# LuxLogger_V2_mcu_pwr.net
KiCad netlist of a schematic drawn in Altium Designer
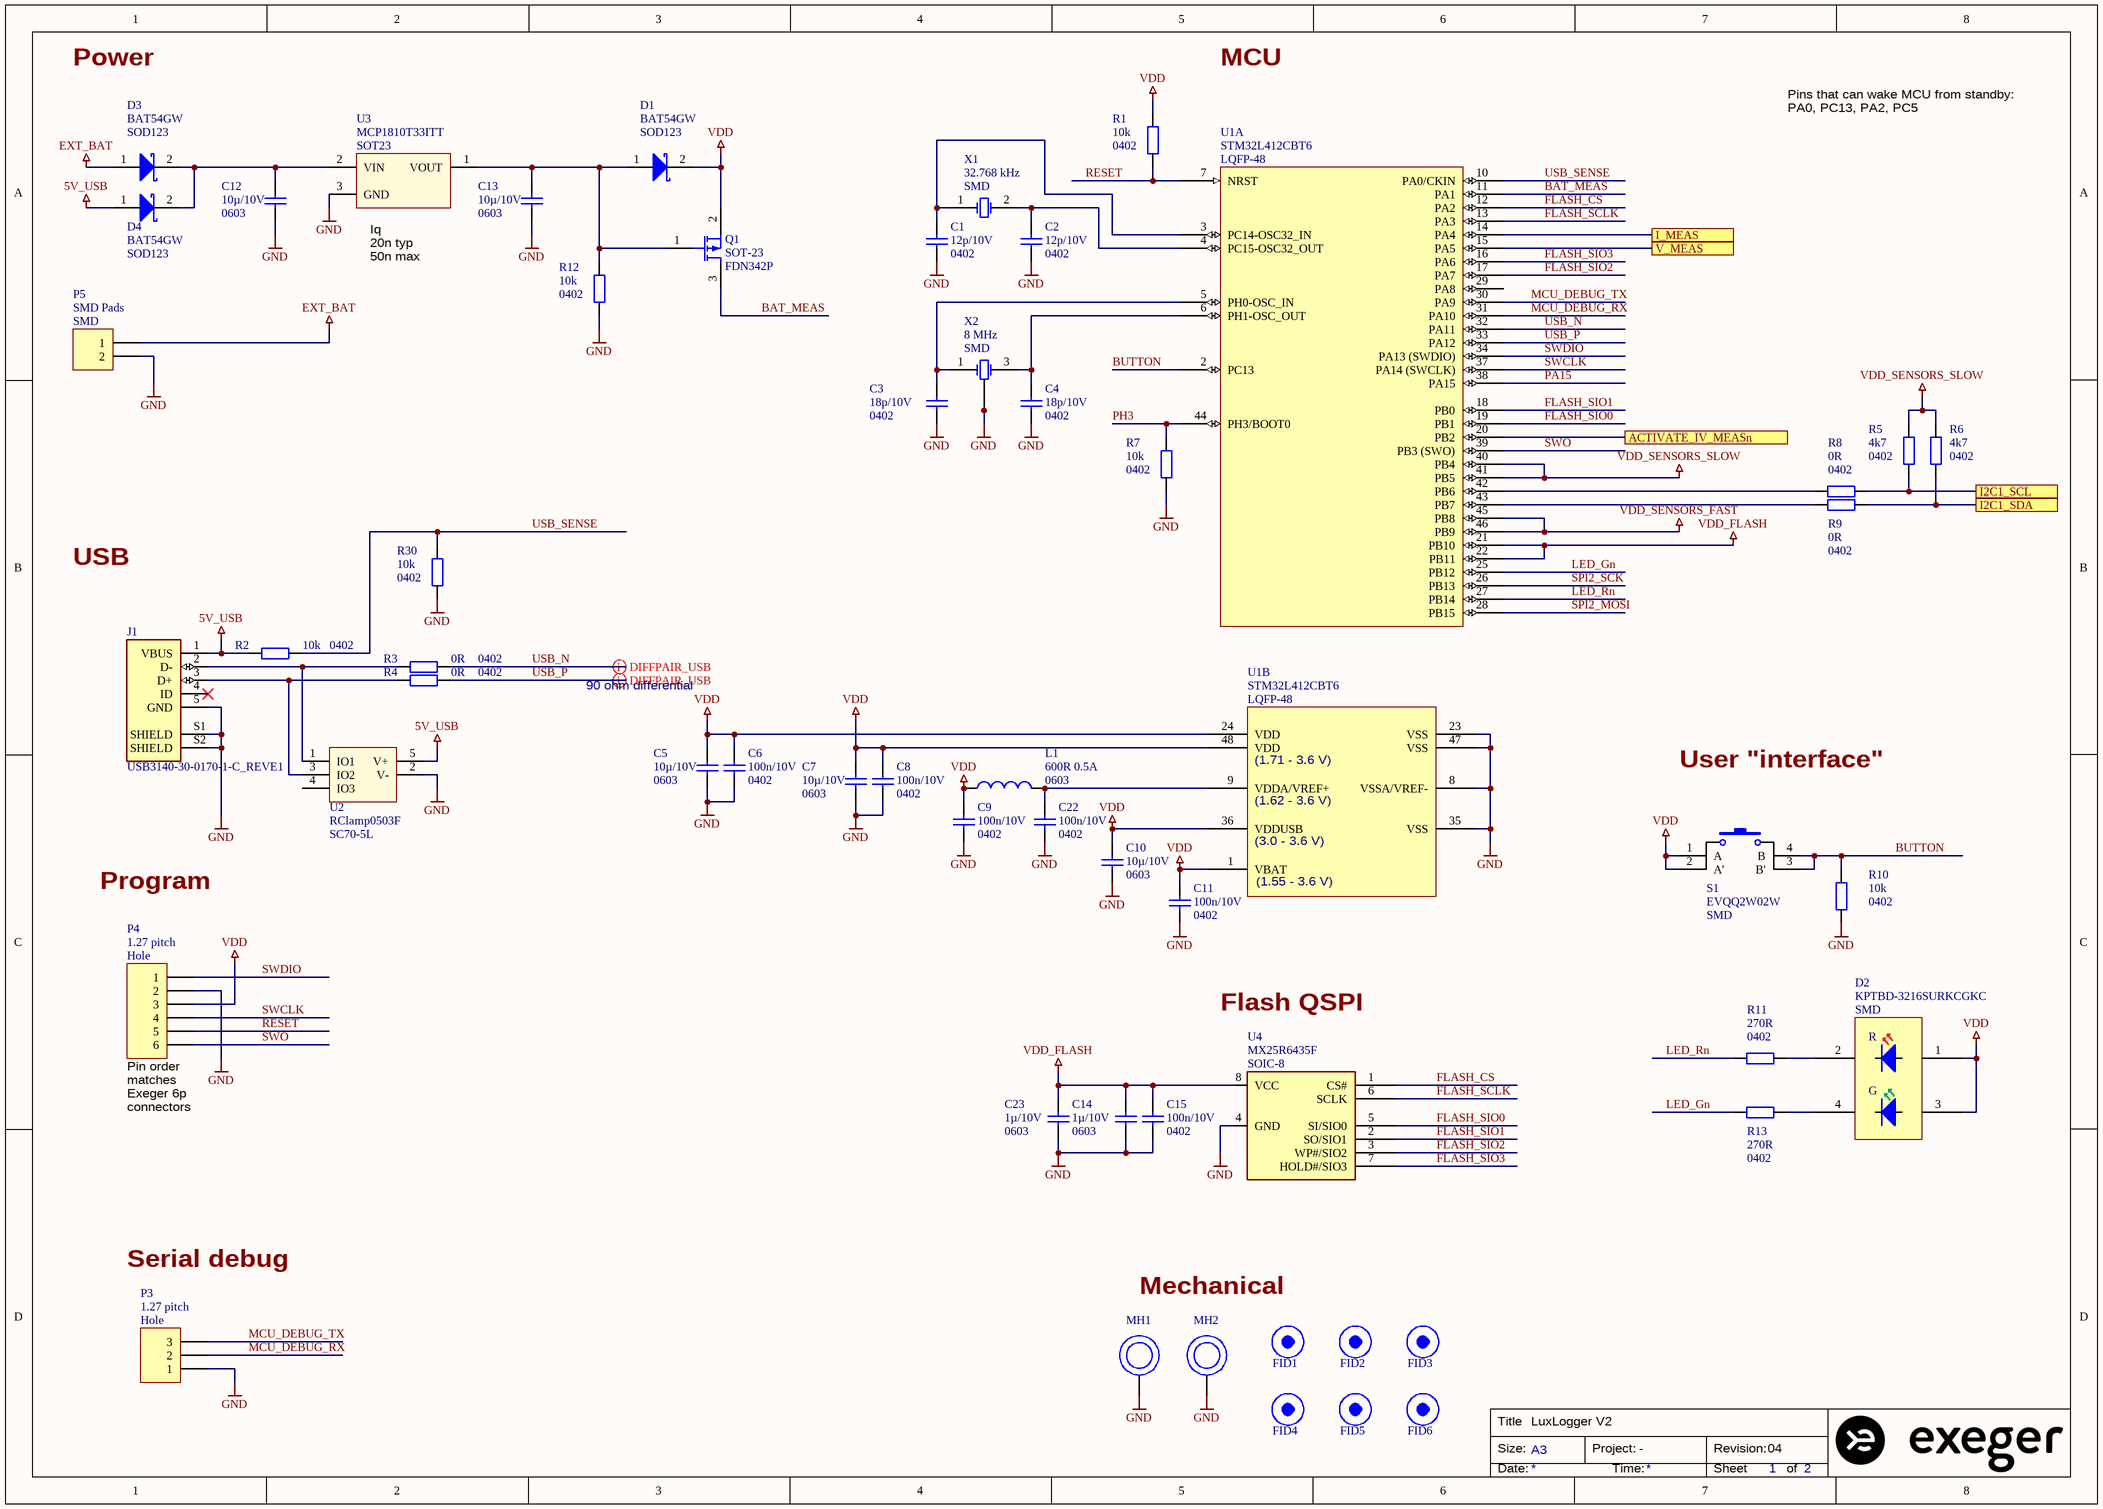
[diagram p0: LuxLogger_V2_mcu_pwr.SchDoc]

(export (version "E")
  (design (tool "Eeschema 10.0.6"))
  (components
    (comp (ref "C1")
      (value "~")
      (footprint "CAP0402")
      (description "Capacitor")
      (fields (field (name "SPECIFICATION") "12p/10V") (field (name "PACKAGE") "0402"))
      (libsource (lib "Miscellaneous Devices") (part "Cap"))
    )
    (comp (ref "C2")
      (value "~")
      (footprint "CAP0402")
      (description "Capacitor")
      (fields (field (name "SPECIFICATION") "12p/10V") (field (name "PACKAGE") "0402"))
      (libsource (lib "Miscellaneous Devices") (part "Cap"))
    )
    (comp (ref "C3")
      (value "~")
      (footprint "CAP0402")
      (description "Capacitor")
      (fields (field (name "SPECIFICATION") "18p/10V") (field (name "PACKAGE") "0402"))
      (libsource (lib "Miscellaneous Devices") (part "Cap"))
    )
    (comp (ref "C4")
      (value "~")
      (footprint "CAP0402")
      (description "Capacitor")
      (fields (field (name "SPECIFICATION") "18p/10V") (field (name "PACKAGE") "0402"))
      (libsource (lib "Miscellaneous Devices") (part "Cap"))
    )
    (comp (ref "C5")
      (value "~")
      (footprint "CAP0603")
      (description "Capacitor")
      (fields (field (name "SPECIFICATION") "10µ/10V") (field (name "PACKAGE") "0603"))
      (libsource (lib "Miscellaneous Devices") (part "Cap"))
    )
    (comp (ref "C6")
      (value "~")
      (footprint "CAP0402")
      (description "Capacitor")
      (fields (field (name "SPECIFICATION") "100n/10V") (field (name "PACKAGE") "0402"))
      (libsource (lib "Miscellaneous Devices") (part "Cap"))
    )
    (comp (ref "C7")
      (value "~")
      (footprint "CAP0603")
      (description "Capacitor")
      (fields (field (name "SPECIFICATION") "10µ/10V") (field (name "PACKAGE") "0603"))
      (libsource (lib "Miscellaneous Devices") (part "Cap"))
    )
    (comp (ref "C8")
      (value "~")
      (footprint "CAP0402")
      (description "Capacitor")
      (fields (field (name "SPECIFICATION") "100n/10V") (field (name "PACKAGE") "0402"))
      (libsource (lib "Miscellaneous Devices") (part "Cap"))
    )
    (comp (ref "C9")
      (value "~")
      (footprint "CAP0402")
      (description "Capacitor")
      (fields (field (name "SPECIFICATION") "100n/10V") (field (name "PACKAGE") "0402"))
      (libsource (lib "Miscellaneous Devices") (part "Cap"))
    )
    (comp (ref "C10")
      (value "~")
      (footprint "CAP0603")
      (description "Capacitor")
      (fields (field (name "SPECIFICATION") "10µ/10V") (field (name "PACKAGE") "0603"))
      (libsource (lib "Miscellaneous Devices") (part "Cap"))
    )
    (comp (ref "C11")
      (value "~")
      (footprint "CAP0402")
      (description "Capacitor")
      (fields (field (name "SPECIFICATION") "100n/10V") (field (name "PACKAGE") "0402"))
      (libsource (lib "Miscellaneous Devices") (part "Cap"))
    )
    (comp (ref "C12")
      (value "~")
      (footprint "CAP0603")
      (description "Capacitor")
      (fields (field (name "SPECIFICATION") "10µ/10V") (field (name "PACKAGE") "0603"))
      (libsource (lib "Miscellaneous Devices") (part "Cap"))
    )
    (comp (ref "C13")
      (value "~")
      (footprint "CAP0603")
      (description "Capacitor")
      (fields (field (name "SPECIFICATION") "10µ/10V") (field (name "PACKAGE") "0603"))
      (libsource (lib "Miscellaneous Devices") (part "Cap"))
    )
    (comp (ref "C14")
      (value "~")
      (footprint "CAP0603")
      (description "Capacitor")
      (fields (field (name "SPECIFICATION") "1µ/10V") (field (name "PACKAGE") "0603"))
      (libsource (lib "Miscellaneous Devices") (part "Cap"))
    )
    (comp (ref "C15")
      (value "~")
      (footprint "CAP0402")
      (description "Capacitor")
      (fields (field (name "SPECIFICATION") "100n/10V") (field (name "PACKAGE") "0402"))
      (libsource (lib "Miscellaneous Devices") (part "Cap"))
    )
    (comp (ref "C22")
      (value "~")
      (footprint "CAP0402")
      (description "Capacitor")
      (fields (field (name "SPECIFICATION") "100n/10V") (field (name "PACKAGE") "0402"))
      (libsource (lib "Miscellaneous Devices") (part "Cap"))
    )
    (comp (ref "C23")
      (value "~")
      (footprint "CAP0603")
      (description "Capacitor")
      (fields (field (name "SPECIFICATION") "1µ/10V") (field (name "PACKAGE") "0603"))
      (libsource (lib "Miscellaneous Devices") (part "Cap"))
    )
    (comp (ref "D1")
      (value "Alternative ON BAT54T1GOSCT-ND")
      (footprint "SOD123 SODFL360X130-2N")
      (description "Schottky Diode")
      (fields
        (field (name "MANUFACTURER") "NEXPERIA")
        (field (name "PACKAGE") "SOD123")
        (field (name "SPECIFICATION") "BAT54GW")
      )
      (libsource (lib "Exeger_schematic_library") (part "D Schottky"))
    )
    (comp (ref "D2")
      (value "~")
      (footprint "KPTBD-3216SURKCGKC")
      (description "Red/green LED")
      (fields
        (field (name "MANUFACTURER") "KINGBRIGHT")
        (field (name "PACKAGE") "SMD")
        (field (name "SPECIFICATION") "KPTBD-3216SURKCGKC")
      )
      (libsource (lib "Exeger_schematic_library") (part "LED_RG"))
    )
    (comp (ref "D3")
      (value "Alternative ON BAT54T1GOSCT-ND")
      (footprint "SOD123 SODFL360X130-2N")
      (description "Schottky Diode")
      (fields
        (field (name "MANUFACTURER") "NEXPERIA")
        (field (name "PACKAGE") "SOD123")
        (field (name "SPECIFICATION") "BAT54GW")
      )
      (libsource (lib "Exeger_schematic_library") (part "D Schottky"))
    )
    (comp (ref "D4")
      (value "Alternative ON BAT54T1GOSCT-ND")
      (footprint "SOD123 SODFL360X130-2N")
      (description "Schottky Diode")
      (fields
        (field (name "MANUFACTURER") "NEXPERIA")
        (field (name "PACKAGE") "SOD123")
        (field (name "SPECIFICATION") "BAT54GW")
      )
      (libsource (lib "Exeger_schematic_library") (part "D Schottky"))
    )
    (comp (ref "FID1")
      (value "Fiducial")
      (footprint "FIDUCIAL_02_small")
      (libsource (lib "Exeger_schematic_library") (part "Fiducial"))
    )
    (comp (ref "FID2")
      (value "Fiducial")
      (footprint "FIDUCIAL_02_small")
      (libsource (lib "Exeger_schematic_library") (part "Fiducial"))
    )
    (comp (ref "FID3")
      (value "Fiducial")
      (footprint "FIDUCIAL_02_small")
      (libsource (lib "Exeger_schematic_library") (part "Fiducial"))
    )
    (comp (ref "FID4")
      (value "Fiducial")
      (footprint "FIDUCIAL_02_small")
      (libsource (lib "Exeger_schematic_library") (part "Fiducial"))
    )
    (comp (ref "FID5")
      (value "Fiducial")
      (footprint "FIDUCIAL_02_small")
      (libsource (lib "Exeger_schematic_library") (part "Fiducial"))
    )
    (comp (ref "FID6")
      (value "Fiducial")
      (footprint "FIDUCIAL_02_small")
      (libsource (lib "Exeger_schematic_library") (part "Fiducial"))
    )
    (comp (ref "J1")
      (value "USB3140-30-0170-1-C_REVE1")
      (footprint "GCT_USB3140-30-0170-1-C_REVE1")
      (description "USB - micro B USB 2.0 Receptacle Connector 5 Position Surface Mount, Through Hole")
      (fields (field (name "MP") "USB3140-30-0170-1-C") (field (name "MF") "Global Connector Technology"))
      (libsource (lib "USB3140-30-0170-1-C_REVE1") (part "USB3140-30-0170-1-C_REVE1"))
    )
    (comp (ref "L1")
      (value "~")
      (footprint "CAP0603")
      (description "Inductor")
      (fields
        (field (name "SPECIFICATION") "600R 0.5A")
        (field (name "PACKAGE") "0603")
        (field (name "MANUFACTURER") "MURATA")
      )
      (libsource (lib "Miscellaneous Devices") (part "Inductor"))
    )
    (comp (ref "MH1")
      (value "Mounting hole")
      (footprint "HOLE_PLATED_2300um")
      (libsource (lib "Exeger_schematic_library") (part "Mounting hole"))
    )
    (comp (ref "MH2")
      (value "Mounting hole")
      (footprint "HOLE_PLATED_2300um")
      (libsource (lib "Exeger_schematic_library") (part "Mounting hole"))
    )
    (comp (ref "P3")
      (value "~")
      (footprint "Header 1x3 1.27")
      (description "Header, 3-Pin")
      (fields (field (name "PACKAGE") "Hole") (field (name "SPECIFICATION") "1.27 pitch"))
      (libsource (lib "Miscellaneous Connectors") (part "Header 3"))
    )
    (comp (ref "P4")
      (value "~")
      (footprint "Header 1x6 1.27")
      (description "Header, 6-Pin")
      (fields (field (name "PACKAGE") "Hole") (field (name "SPECIFICATION") "1.27 pitch"))
      (libsource (lib "Miscellaneous Connectors") (part "Header 6"))
    )
    (comp (ref "P5")
      (value "~")
      (footprint "2x1 blank pads_2")
      (description "Header, 2-Pin")
      (fields (field (name "PACKAGE") "SMD") (field (name "SPECIFICATION") "SMD Pads"))
      (libsource (lib "Miscellaneous Connectors") (part "Header 2"))
    )
    (comp (ref "Q1")
      (value "~")
      (footprint "SOT23-3")
      (description "P-Channel MOSFET")
      (fields
        (field (name "MANUFACTURER") "ON")
        (field (name "PACKAGE") "SOT-23")
        (field (name "SPECIFICATION") "FDN342P")
      )
      (libsource (lib "Exeger_schematic_library") (part "MOSFET-P"))
    )
    (comp (ref "R1")
      (value "~")
      (footprint "RES0402")
      (description "Resistor")
      (fields (field (name "PACKAGE") "0402") (field (name "SPECIFICATION") "10k"))
      (libsource (lib "") (part "Res2_1"))
    )
    (comp (ref "R2")
      (value "~")
      (footprint "RES0402")
      (description "Resistor")
      (fields (field (name "PACKAGE") "0402") (field (name "SPECIFICATION") "10k"))
      (libsource (lib "Miscellaneous Devices") (part "Res2"))
    )
    (comp (ref "R3")
      (value "~")
      (footprint "RES0402")
      (description "Resistor")
      (fields (field (name "PACKAGE") "0402") (field (name "SPECIFICATION") "0R"))
      (libsource (lib "Miscellaneous Devices") (part "Res2"))
    )
    (comp (ref "R4")
      (value "~")
      (footprint "RES0402")
      (description "Resistor")
      (fields (field (name "PACKAGE") "0402") (field (name "SPECIFICATION") "0R"))
      (libsource (lib "Miscellaneous Devices") (part "Res2"))
    )
    (comp (ref "R5")
      (value "~")
      (footprint "RES0402")
      (description "Resistor")
      (fields (field (name "PACKAGE") "0402") (field (name "SPECIFICATION") "4k7"))
      (libsource (lib "") (part "Res2_1"))
    )
    (comp (ref "R6")
      (value "~")
      (footprint "RES0402")
      (description "Resistor")
      (fields (field (name "PACKAGE") "0402") (field (name "SPECIFICATION") "4k7"))
      (libsource (lib "") (part "Res2_1"))
    )
    (comp (ref "R7")
      (value "~")
      (footprint "RES0402")
      (description "Resistor")
      (fields (field (name "PACKAGE") "0402") (field (name "SPECIFICATION") "10k"))
      (libsource (lib "") (part "Res2_1"))
    )
    (comp (ref "R8")
      (value "~")
      (footprint "RES0402")
      (description "Resistor")
      (fields (field (name "PACKAGE") "0402") (field (name "SPECIFICATION") "0R"))
      (libsource (lib "Miscellaneous Devices") (part "Res2"))
    )
    (comp (ref "R9")
      (value "~")
      (footprint "RES0402")
      (description "Resistor")
      (fields (field (name "PACKAGE") "0402") (field (name "SPECIFICATION") "0R"))
      (libsource (lib "Miscellaneous Devices") (part "Res2"))
    )
    (comp (ref "R10")
      (value "~")
      (footprint "RES0402")
      (description "Resistor")
      (fields (field (name "PACKAGE") "0402") (field (name "SPECIFICATION") "10k"))
      (libsource (lib "") (part "Res2_1"))
    )
    (comp (ref "R11")
      (value "~")
      (footprint "RES0402")
      (description "Resistor")
      (fields (field (name "PACKAGE") "0402") (field (name "SPECIFICATION") "270R"))
      (libsource (lib "Miscellaneous Devices") (part "Res2"))
    )
    (comp (ref "R12")
      (value "~")
      (footprint "RES0402")
      (description "Resistor")
      (fields (field (name "PACKAGE") "0402") (field (name "SPECIFICATION") "10k"))
      (libsource (lib "") (part "Res2_1"))
    )
    (comp (ref "R13")
      (value "~")
      (footprint "RES0402")
      (description "Resistor")
      (fields (field (name "PACKAGE") "0402") (field (name "SPECIFICATION") "270R"))
      (libsource (lib "Miscellaneous Devices") (part "Res2"))
    )
    (comp (ref "R30")
      (value "~")
      (footprint "RES0402")
      (description "Resistor")
      (fields (field (name "PACKAGE") "0402") (field (name "SPECIFICATION") "10k"))
      (libsource (lib "") (part "Res2_1"))
    )
    (comp (ref "S1")
      (value "~")
      (footprint "EVQQ2W02W")
      (description "Switch")
      (fields
        (field (name "MANUFACTURER") "PANASONIC")
        (field (name "SPECIFICATION") "EVQQ2W02W")
        (field (name "PACKAGE") "SMD")
      )
      (libsource (lib "Exeger_schematic_library") (part "SW_EVQQ2"))
    )
    (comp (ref "U1")
      (value "~")
      (footprint "TSQFP50P900X900X160-48N")
      (description "MCU")
      (fields
        (field (name "SPECIFICATION") "STM32L412CBT6")
        (field (name "PACKAGE") "LQFP-48")
        (field (name "MANUFACTURER") "ST")
      )
      (libsource (lib "Exeger_schematic_library") (part "STM32L412CB_2"))
    )
    (comp (ref "U2")
      (value "~")
      (footprint "SC-70 5L")
      (description "TVS array USB")
      (fields
        (field (name "MANUFACTURER") "SEMTECH")
        (field (name "PACKAGE") "SC70-5L")
        (field (name "SPECIFICATION") "RClamp0503F")
      )
      (libsource (lib "Exeger_schematic_library") (part "RClamp0503F"))
    )
    (comp (ref "U3")
      (value "~")
      (footprint "SOT23-3")
      (description "3V3 LDO low iq")
      (fields
        (field (name "MANUFACTURER") "MICROCHIP")
        (field (name "SPECIFICATION") "MCP1810T33ITT")
        (field (name "PACKAGE") "SOT23")
      )
      (libsource (lib "Exeger_schematic_library") (part "MCP1810TxxxTT"))
    )
    (comp (ref "U4")
      (value "~")
      (footprint "SO_8_W")
      (description "ULTRA LOW POWER, 64M-BIT FLASH MEMORY")
      (fields
        (field (name "MANUFACTURER") "Macronix")
        (field (name "PACKAGE") "SOIC-8")
        (field (name "SPECIFICATION") "MX25R6435F")
      )
      (libsource (lib "Exeger_schematic_library") (part "MX25R6435F_SO8"))
    )
    (comp (ref "X1")
      (value "~")
      (footprint "FC-135")
      (description "32.768 kHz Crystal")
      (fields
        (field (name "MANUFACTURER") "EPSON")
        (field (name "PACKAGE") "SMD")
        (field (name "SPECIFICATION") "32.768 kHz")
      )
      (libsource (lib "Exeger_schematic_library") (part "XTAL 2pin"))
    )
    (comp (ref "X2")
      (value "~")
      (footprint "ABM3B")
      (description "Crystal")
      (fields
        (field (name "MANUFACTURER") "ABRACON")
        (field (name "SPECIFICATION") "8 MHz")
        (field (name "PACKAGE") "SMD")
      )
      (libsource (lib "Exeger_schematic_library") (part "XTAL 4pin"))
    )
  )
  (nets
    (net (code "1") (name "/ACTIVATE_IV_MEASn") (class "Default")
      (node (ref "U1") (pin "20") (pinfunction "PB2_20") (pintype "bidirectional"))
    )
    (net (code "2") (name "/BAT_MEAS") (class "Default")
      (node (ref "Q1") (pin "3") (pinfunction "D_3") (pintype "passive"))
      (node (ref "U1") (pin "11") (pinfunction "PA1_11") (pintype "bidirectional"))
    )
    (net (code "3") (name "/BUTTON") (class "Default")
      (node (ref "R10") (pin "2") (pinfunction "2_2") (pintype "passive"))
      (node (ref "S1") (pin "3") (pinfunction "B'_3") (pintype "passive"))
      (node (ref "S1") (pin "4") (pinfunction "B_4") (pintype "passive"))
      (node (ref "U1") (pin "2") (pinfunction "PC13_2") (pintype "bidirectional"))
    )
    (net (code "4") (name "/FLASH_CS") (class "Default")
      (node (ref "U1") (pin "12") (pinfunction "PA2_12") (pintype "bidirectional"))
      (node (ref "U4") (pin "1") (pinfunction "CS#_1") (pintype "passive"))
    )
    (net (code "5") (name "/FLASH_SCLK") (class "Default")
      (node (ref "U1") (pin "13") (pinfunction "PA3_13") (pintype "bidirectional"))
      (node (ref "U4") (pin "6") (pinfunction "SCLK_6") (pintype "passive"))
    )
    (net (code "6") (name "/FLASH_SIO0") (class "Default")
      (node (ref "U1") (pin "19") (pinfunction "PB1_19") (pintype "bidirectional"))
      (node (ref "U4") (pin "5") (pinfunction "SI/SIO0_5") (pintype "passive"))
    )
    (net (code "7") (name "/FLASH_SIO1") (class "Default")
      (node (ref "U1") (pin "18") (pinfunction "PB0_18") (pintype "bidirectional"))
      (node (ref "U4") (pin "2") (pinfunction "SO/SIO1_2") (pintype "passive"))
    )
    (net (code "8") (name "/FLASH_SIO2") (class "Default")
      (node (ref "U1") (pin "17") (pinfunction "PA7_17") (pintype "bidirectional"))
      (node (ref "U4") (pin "3") (pinfunction "WP#/SIO2_3") (pintype "passive"))
    )
    (net (code "9") (name "/FLASH_SIO3") (class "Default")
      (node (ref "U1") (pin "16") (pinfunction "PA6_16") (pintype "bidirectional"))
      (node (ref "U4") (pin "7") (pinfunction "HOLD#/SIO3_7") (pintype "passive"))
    )
    (net (code "10") (name "/I2C1_SCL") (class "Default")
      (node (ref "R5") (pin "1") (pinfunction "1_1") (pintype "passive"))
      (node (ref "R8") (pin "1") (pinfunction "1_1") (pintype "passive"))
    )
    (net (code "11") (name "/I2C1_SDA") (class "Default")
      (node (ref "R6") (pin "1") (pinfunction "1_1") (pintype "passive"))
      (node (ref "R9") (pin "1") (pinfunction "1_1") (pintype "passive"))
    )
    (net (code "12") (name "/I_MEAS") (class "Default")
      (node (ref "U1") (pin "14") (pinfunction "PA4_14") (pintype "bidirectional"))
    )
    (net (code "13") (name "/LED_Gn") (class "Default")
      (node (ref "R13") (pin "2") (pinfunction "2_2") (pintype "passive"))
      (node (ref "U1") (pin "25") (pinfunction "PB12_25") (pintype "bidirectional"))
    )
    (net (code "14") (name "/LED_Rn") (class "Default")
      (node (ref "R11") (pin "2") (pinfunction "2_2") (pintype "passive"))
      (node (ref "U1") (pin "27") (pinfunction "PB14_27") (pintype "bidirectional"))
    )
    (net (code "15") (name "/MCU_DEBUG_RX") (class "Default")
      (node (ref "P3") (pin "2") (pinfunction "2_2") (pintype "passive"))
      (node (ref "U1") (pin "31") (pinfunction "PA10_31") (pintype "bidirectional"))
    )
    (net (code "16") (name "/MCU_DEBUG_TX") (class "Default")
      (node (ref "P3") (pin "3") (pinfunction "3_3") (pintype "passive"))
      (node (ref "U1") (pin "30") (pinfunction "PA9_30") (pintype "bidirectional"))
    )
    (net (code "17") (name "/PA15") (class "Default")
      (node (ref "U1") (pin "38") (pinfunction "PA15_38") (pintype "bidirectional"))
    )
    (net (code "18") (name "/PH3") (class "Default")
      (node (ref "R7") (pin "2") (pinfunction "2_2") (pintype "passive"))
      (node (ref "U1") (pin "44") (pinfunction "PH3/BOOT0_44") (pintype "bidirectional"))
    )
    (net (code "19") (name "/RESET") (class "Default")
      (node (ref "P4") (pin "5") (pinfunction "5_5") (pintype "passive"))
      (node (ref "R1") (pin "1") (pinfunction "1_1") (pintype "passive"))
      (node (ref "U1") (pin "7") (pinfunction "NRST_7") (pintype "input"))
    )
    (net (code "20") (name "/SPI2_MOSI") (class "Default")
      (node (ref "U1") (pin "28") (pinfunction "PB15_28") (pintype "bidirectional"))
    )
    (net (code "21") (name "/SPI2_SCK") (class "Default")
      (node (ref "U1") (pin "26") (pinfunction "PB13_26") (pintype "bidirectional"))
    )
    (net (code "22") (name "/SWCLK") (class "Default")
      (node (ref "P4") (pin "4") (pinfunction "4_4") (pintype "passive"))
      (node (ref "U1") (pin "37") (pinfunction "PA14_(SWCLK)_37") (pintype "bidirectional"))
    )
    (net (code "23") (name "/SWDIO") (class "Default")
      (node (ref "P4") (pin "1") (pinfunction "1_1") (pintype "passive"))
      (node (ref "U1") (pin "34") (pinfunction "PA13_(SWDIO)_34") (pintype "bidirectional"))
    )
    (net (code "24") (name "/SWO") (class "Default")
      (node (ref "P4") (pin "6") (pinfunction "6_6") (pintype "passive"))
      (node (ref "U1") (pin "39") (pinfunction "PB3_(SWO)_39") (pintype "bidirectional"))
    )
    (net (code "25") (name "/USB_N") (class "Default")
      (node (ref "R3") (pin "1") (pinfunction "1_1") (pintype "passive"))
      (node (ref "U1") (pin "32") (pinfunction "PA11_32") (pintype "bidirectional"))
    )
    (net (code "26") (name "/USB_P") (class "Default")
      (node (ref "R4") (pin "1") (pinfunction "1_1") (pintype "passive"))
      (node (ref "U1") (pin "33") (pinfunction "PA12_33") (pintype "bidirectional"))
    )
    (net (code "27") (name "/USB_SENSE") (class "Default")
      (node (ref "R2") (pin "1") (pinfunction "1_1") (pintype "passive"))
      (node (ref "R30") (pin "2") (pinfunction "2_2") (pintype "passive"))
      (node (ref "U1") (pin "10") (pinfunction "PA0/CKIN_10") (pintype "bidirectional"))
    )
    (net (code "28") (name "/V_MEAS") (class "Default")
      (node (ref "U1") (pin "15") (pinfunction "PA5_15") (pintype "bidirectional"))
    )
    (net (code "29") (name "5V_USB") (class "Default")
      (node (ref "D4") (pin "1") (pinfunction "A_1") (pintype "passive"))
      (node (ref "J1") (pin "1") (pinfunction "VBUS_1") (pintype "power_in"))
      (node (ref "R2") (pin "2") (pinfunction "2_2") (pintype "passive"))
      (node (ref "U2") (pin "5") (pinfunction "V+_5") (pintype "power_in"))
    )
    (net (code "30") (name "EXT_BAT") (class "Default")
      (node (ref "D3") (pin "1") (pinfunction "A_1") (pintype "passive"))
      (node (ref "P5") (pin "1") (pinfunction "1_1") (pintype "passive"))
    )
    (net (code "31") (name "GND") (class "Default")
      (node (ref "C1") (pin "1") (pinfunction "1_1") (pintype "passive"))
      (node (ref "C10") (pin "1") (pinfunction "1_1") (pintype "passive"))
      (node (ref "C11") (pin "1") (pinfunction "1_1") (pintype "passive"))
      (node (ref "C12") (pin "1") (pinfunction "1_1") (pintype "passive"))
      (node (ref "C13") (pin "1") (pinfunction "1_1") (pintype "passive"))
      (node (ref "C14") (pin "1") (pinfunction "1_1") (pintype "passive"))
      (node (ref "C15") (pin "1") (pinfunction "1_1") (pintype "passive"))
      (node (ref "C2") (pin "1") (pinfunction "1_1") (pintype "passive"))
      (node (ref "C22") (pin "1") (pinfunction "1_1") (pintype "passive"))
      (node (ref "C23") (pin "1") (pinfunction "1_1") (pintype "passive"))
      (node (ref "C3") (pin "1") (pinfunction "1_1") (pintype "passive"))
      (node (ref "C4") (pin "1") (pinfunction "1_1") (pintype "passive"))
      (node (ref "C5") (pin "1") (pinfunction "1_1") (pintype "passive"))
      (node (ref "C6") (pin "1") (pinfunction "1_1") (pintype "passive"))
      (node (ref "C7") (pin "1") (pinfunction "1_1") (pintype "passive"))
      (node (ref "C8") (pin "1") (pinfunction "1_1") (pintype "passive"))
      (node (ref "C9") (pin "1") (pinfunction "1_1") (pintype "passive"))
      (node (ref "J1") (pin "5") (pinfunction "GND_5") (pintype "power_in"))
      (node (ref "J1") (pin "S1") (pinfunction "SHIELD_S1") (pintype "passive"))
      (node (ref "J1") (pin "S2") (pinfunction "SHIELD_S2") (pintype "passive"))
      (node (ref "MH1") (pin "1") (pinfunction "1_1") (pintype "passive"))
      (node (ref "MH2") (pin "1") (pinfunction "1_1") (pintype "passive"))
      (node (ref "P3") (pin "1") (pinfunction "1_1") (pintype "passive"))
      (node (ref "P4") (pin "2") (pinfunction "2_2") (pintype "passive"))
      (node (ref "P5") (pin "2") (pinfunction "2_2") (pintype "passive"))
      (node (ref "R10") (pin "1") (pinfunction "1_1") (pintype "passive"))
      (node (ref "R12") (pin "1") (pinfunction "1_1") (pintype "passive"))
      (node (ref "R30") (pin "1") (pinfunction "1_1") (pintype "passive"))
      (node (ref "R7") (pin "1") (pinfunction "1_1") (pintype "passive"))
      (node (ref "U1") (pin "23") (pinfunction "VSS_23") (pintype "power_in"))
      (node (ref "U1") (pin "35") (pinfunction "VSS_35") (pintype "power_in"))
      (node (ref "U1") (pin "47") (pinfunction "VSS_47") (pintype "power_in"))
      (node (ref "U1") (pin "8") (pinfunction "VSSA/VREF-_8") (pintype "power_in"))
      (node (ref "U2") (pin "2") (pinfunction "V-_2") (pintype "power_in"))
      (node (ref "U3") (pin "3") (pinfunction "GND_3") (pintype "power_in"))
      (node (ref "U4") (pin "4") (pinfunction "GND_4") (pintype "passive"))
      (node (ref "X2") (pin "2") (pinfunction "GND_2") (pintype "passive"))
      (node (ref "X2") (pin "4") (pinfunction "GND_4") (pintype "passive"))
    )
    (net (code "32") (name "Net-(D1-A)") (class "Default")
      (node (ref "C13") (pin "2") (pinfunction "2_2") (pintype "passive"))
      (node (ref "D1") (pin "1") (pinfunction "A_1") (pintype "passive"))
      (node (ref "Q1") (pin "1") (pinfunction "G_1") (pintype "passive"))
      (node (ref "R12") (pin "2") (pinfunction "2_2") (pintype "passive"))
      (node (ref "U3") (pin "1") (pinfunction "VOUT_1") (pintype "power_in"))
    )
    (net (code "33") (name "Net-(D2-G_K)") (class "Default")
      (node (ref "D2") (pin "4") (pinfunction "G_K_4") (pintype "passive"))
      (node (ref "R13") (pin "1") (pinfunction "1_1") (pintype "passive"))
    )
    (net (code "34") (name "Net-(D2-R_K)") (class "Default")
      (node (ref "D2") (pin "2") (pinfunction "R_K_2") (pintype "passive"))
      (node (ref "R11") (pin "1") (pinfunction "1_1") (pintype "passive"))
    )
    (net (code "35") (name "Net-(D3-K)") (class "Default")
      (node (ref "C12") (pin "2") (pinfunction "2_2") (pintype "passive"))
      (node (ref "D3") (pin "2") (pinfunction "K_2") (pintype "passive"))
      (node (ref "D4") (pin "2") (pinfunction "K_2") (pintype "passive"))
      (node (ref "U3") (pin "2") (pinfunction "VIN_2") (pintype "passive"))
    )
    (net (code "36") (name "Net-(J1-D+)") (class "Default")
      (node (ref "J1") (pin "3") (pinfunction "D+_3") (pintype "bidirectional"))
      (node (ref "R4") (pin "2") (pinfunction "2_2") (pintype "passive"))
      (node (ref "U2") (pin "3") (pinfunction "IO2_3") (pintype "power_in"))
    )
    (net (code "37") (name "Net-(J1-D-)") (class "Default")
      (node (ref "J1") (pin "2") (pinfunction "D-_2") (pintype "bidirectional"))
      (node (ref "R3") (pin "2") (pinfunction "2_2") (pintype "passive"))
      (node (ref "U2") (pin "1") (pinfunction "IO1_1") (pintype "power_in"))
    )
    (net (code "38") (name "Net-(U1A-PB6)") (class "Default")
      (node (ref "R8") (pin "2") (pinfunction "2_2") (pintype "passive"))
      (node (ref "U1") (pin "42") (pinfunction "PB6_42") (pintype "bidirectional"))
    )
    (net (code "39") (name "Net-(U1A-PB7)") (class "Default")
      (node (ref "R9") (pin "2") (pinfunction "2_2") (pintype "passive"))
      (node (ref "U1") (pin "43") (pinfunction "PB7_43") (pintype "bidirectional"))
    )
    (net (code "40") (name "Net-(U1A-PC14-OSC32_IN)") (class "Default")
      (node (ref "C1") (pin "2") (pinfunction "2_2") (pintype "passive"))
      (node (ref "U1") (pin "3") (pinfunction "PC14-OSC32_IN_3") (pintype "bidirectional"))
      (node (ref "X1") (pin "1") (pinfunction "OSC1_1") (pintype "passive"))
    )
    (net (code "41") (name "Net-(U1A-PC15-OSC32_OUT)") (class "Default")
      (node (ref "C2") (pin "2") (pinfunction "2_2") (pintype "passive"))
      (node (ref "U1") (pin "4") (pinfunction "PC15-OSC32_OUT_4") (pintype "bidirectional"))
      (node (ref "X1") (pin "2") (pinfunction "OSC2_2") (pintype "passive"))
    )
    (net (code "42") (name "Net-(U1A-PH0-OSC_IN)") (class "Default")
      (node (ref "C3") (pin "2") (pinfunction "2_2") (pintype "passive"))
      (node (ref "U1") (pin "5") (pinfunction "PH0-OSC_IN_5") (pintype "bidirectional"))
      (node (ref "X2") (pin "1") (pinfunction "OSC1_1") (pintype "passive"))
    )
    (net (code "43") (name "Net-(U1A-PH1-OSC_OUT)") (class "Default")
      (node (ref "C4") (pin "2") (pinfunction "2_2") (pintype "passive"))
      (node (ref "U1") (pin "6") (pinfunction "PH1-OSC_OUT_6") (pintype "bidirectional"))
      (node (ref "X2") (pin "3") (pinfunction "OSC2_3") (pintype "passive"))
    )
    (net (code "44") (name "Net-(U1B-VDDA{slash}VREF+)") (class "Default")
      (node (ref "C22") (pin "2") (pinfunction "2_2") (pintype "passive"))
      (node (ref "L1") (pin "2") (pinfunction "2_2") (pintype "passive"))
      (node (ref "U1") (pin "9") (pinfunction "VDDA/VREF+_9") (pintype "power_in"))
    )
    (net (code "45") (name "VDD") (class "Default")
      (node (ref "C10") (pin "2") (pinfunction "2_2") (pintype "passive"))
      (node (ref "C11") (pin "2") (pinfunction "2_2") (pintype "passive"))
      (node (ref "C5") (pin "2") (pinfunction "2_2") (pintype "passive"))
      (node (ref "C6") (pin "2") (pinfunction "2_2") (pintype "passive"))
      (node (ref "C7") (pin "2") (pinfunction "2_2") (pintype "passive"))
      (node (ref "C8") (pin "2") (pinfunction "2_2") (pintype "passive"))
      (node (ref "C9") (pin "2") (pinfunction "2_2") (pintype "passive"))
      (node (ref "D1") (pin "2") (pinfunction "K_2") (pintype "passive"))
      (node (ref "D2") (pin "1") (pinfunction "R_A_1") (pintype "passive"))
      (node (ref "D2") (pin "3") (pinfunction "G_A_3") (pintype "passive"))
      (node (ref "L1") (pin "1") (pinfunction "1_1") (pintype "passive"))
      (node (ref "P4") (pin "3") (pinfunction "3_3") (pintype "passive"))
      (node (ref "Q1") (pin "2") (pinfunction "S_2") (pintype "passive"))
      (node (ref "R1") (pin "2") (pinfunction "2_2") (pintype "passive"))
      (node (ref "S1") (pin "1") (pinfunction "A_1") (pintype "passive"))
      (node (ref "S1") (pin "2") (pinfunction "A'_2") (pintype "passive"))
      (node (ref "U1") (pin "1") (pinfunction "VBAT_1") (pintype "power_in"))
      (node (ref "U1") (pin "24") (pinfunction "VDD_24") (pintype "power_in"))
      (node (ref "U1") (pin "36") (pinfunction "VDDUSB_36") (pintype "power_in"))
      (node (ref "U1") (pin "48") (pinfunction "VDD_48") (pintype "power_in"))
    )
    (net (code "46") (name "VDD_FLASH") (class "Default")
      (node (ref "C14") (pin "2") (pinfunction "2_2") (pintype "passive"))
      (node (ref "C15") (pin "2") (pinfunction "2_2") (pintype "passive"))
      (node (ref "C23") (pin "2") (pinfunction "2_2") (pintype "passive"))
      (node (ref "U1") (pin "21") (pinfunction "PB10_21") (pintype "bidirectional"))
      (node (ref "U1") (pin "22") (pinfunction "PB11_22") (pintype "bidirectional"))
      (node (ref "U4") (pin "8") (pinfunction "VCC_8") (pintype "passive"))
    )
    (net (code "47") (name "VDD_SENSORS_FAST") (class "Default")
      (node (ref "U1") (pin "45") (pinfunction "PB8_45") (pintype "bidirectional"))
      (node (ref "U1") (pin "46") (pinfunction "PB9_46") (pintype "bidirectional"))
    )
    (net (code "48") (name "VDD_SENSORS_SLOW") (class "Default")
      (node (ref "R5") (pin "2") (pinfunction "2_2") (pintype "passive"))
      (node (ref "R6") (pin "2") (pinfunction "2_2") (pintype "passive"))
      (node (ref "U1") (pin "40") (pinfunction "PB4_40") (pintype "bidirectional"))
      (node (ref "U1") (pin "41") (pinfunction "PB5_41") (pintype "bidirectional"))
    )
    (net (code "49") (name "unconnected-(J1-ID-Pad4)") (class "Default")
      (node (ref "J1") (pin "4") (pinfunction "ID_4") (pintype "passive+no_connect"))
    )
    (net (code "50") (name "unconnected-(U1A-PA8-Pad29)") (class "Default")
      (node (ref "U1") (pin "29") (pinfunction "PA8_29") (pintype "bidirectional"))
    )
    (net (code "51") (name "unconnected-(U2-IO3-Pad4)") (class "Default")
      (node (ref "U2") (pin "4") (pinfunction "IO3_4") (pintype "power_in"))
    )
  )
)
